# SCH_QR_Code_Scanning_Kiosk_PCB_V3_MKR_20.net
KiCad netlist of a schematic drawn in EasyEDA
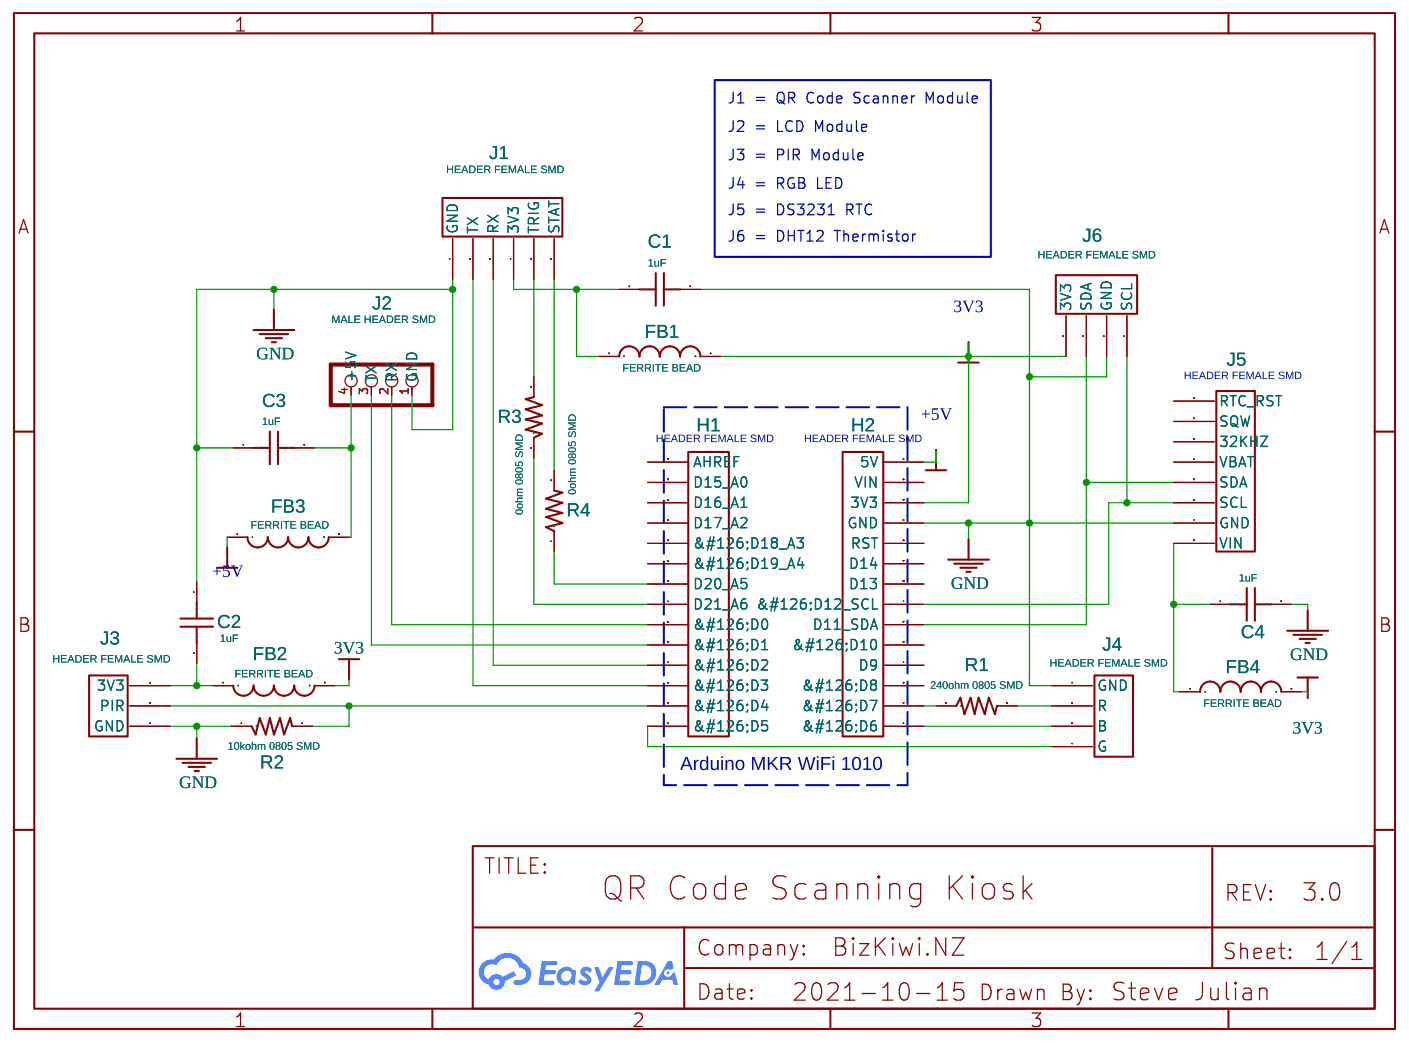
[diagram p0: schematic sheet]

(export (version "E")
  (design (tool "Eeschema 10.0.6"))
  (components
    (comp (ref "C1")
      (value "1uF")
      (fields
        (field (name "BOM_Manufacturer Part") "C0805X104K5RACAUTO")
        (field (name "BOM_Supplier Part") "C141172")
      )
      (libsource (lib "") (part "CAPACITOR CERAMIC 0805 100NF_2"))
    )
    (comp (ref "C2")
      (value "1uF")
      (fields
        (field (name "BOM_Manufacturer Part") "C0805X104K5RACAUTO")
        (field (name "BOM_Supplier Part") "C141172")
      )
      (libsource (lib "") (part "CAPACITOR CERAMIC 0805 100NF"))
    )
    (comp (ref "C3")
      (value "1uF")
      (fields
        (field (name "BOM_Manufacturer Part") "C0805X104K5RACAUTO")
        (field (name "BOM_Supplier Part") "C141172")
      )
      (libsource (lib "") (part "CAPACITOR CERAMIC 0805 100NF_1"))
    )
    (comp (ref "C4")
      (value "1uF")
      (fields
        (field (name "BOM_Manufacturer Part") "C0805X104K5RACAUTO")
        (field (name "BOM_Supplier Part") "C141172")
      )
      (libsource (lib "") (part "CAPACITOR CERAMIC 0805 100NF_2"))
    )
    (comp (ref "FB1") (value "FERRITE BEAD") (libsource (lib "") (part "FERRITE-BEADB")))
    (comp (ref "FB2") (value "FERRITE BEAD") (libsource (lib "") (part "FERRITE-BEADB_1")))
    (comp (ref "FB3") (value "FERRITE BEAD") (libsource (lib "") (part "FERRITE-BEADB_1")))
    (comp (ref "FB4") (value "FERRITE BEAD") (libsource (lib "") (part "FERRITE-BEADB")))
    (comp (ref "H1")
      (value "HEADER FEMALE 2.54MM 1X14 SMD TYPES 1 AND 2")
      (fields
        (field (name "BOM_Manufacturer Part") "SSM-116-L-SV-BE")
        (field (name "BOM_Supplier Part") "SAM11901-ND")
      )
      (libsource (lib "") (part "Unknown_570_-352"))
    )
    (comp (ref "H2")
      (value "HEADER FEMALE 2.54MM 1X14 SMD TYPES 1 AND 2")
      (fields
        (field (name "BOM_Manufacturer Part") "SSM-116-L-SV-BE")
        (field (name "BOM_Supplier Part") "SAM11901-ND")
      )
      (libsource (lib "") (part "Unknown_680_-352"))
    )
    (comp (ref "J1")
      (value "HEADER FEMALE SMD")
      (fields
        (field (name "BOM_Manufacturer Part") "SSM-116-L-SV-BE")
        (field (name "BOM_Supplier Part") "SAM11901-ND")
      )
      (libsource (lib "") (part "HEADER FEMALE 2.54MM 1X6 SMD TYPES 1 AND 2"))
    )
    (comp (ref "J2") (value "MALE HEADER SMD") (libsource (lib "") (part "MALE_HEADER_SMD_1X04")))
    (comp (ref "J3")
      (value "HEADER FEMALE SMD")
      (fields
        (field (name "BOM_Manufacturer Part") "SSM-116-L-SV-BE")
        (field (name "BOM_Supplier Part") "SAM11901-ND")
      )
      (libsource (lib "") (part "HEADER FEMALE 2.54MM 1X3 SMD TYPES 1 AND 2"))
    )
    (comp (ref "J4")
      (value "HEADER FEMALE SMD")
      (fields
        (field (name "BOM_Manufacturer Part") "SSM-116-L-SV-BE")
        (field (name "BOM_Supplier Part") "SAM11901-ND")
      )
      (libsource (lib "") (part "HEADER FEMALE 2.54MM 1X4 SMD TYPES 1 AND 2_1"))
    )
    (comp (ref "J5")
      (value "HEADER FEMALE 2.54MM 1X8 SMD TYPES 1 AND 2")
      (fields
        (field (name "BOM_Manufacturer Part") "SSM-116-L-SV-BE")
        (field (name "BOM_Supplier Part") "SAM11901-ND")
      )
      (libsource (lib "") (part "HEADER FEMALE 2.54MM 1X8 SMD TYPES 1 AND 2"))
    )
    (comp (ref "J6")
      (value "HEADER FEMALE SMD")
      (fields
        (field (name "BOM_Manufacturer Part") "SSM-116-L-SV-BE")
        (field (name "BOM_Supplier Part") "SAM11901-ND")
      )
      (libsource (lib "") (part "HEADER FEMALE 2.54MM 1X4 SMD TYPES 1 AND 2"))
    )
    (comp (ref "R1")
      (value "240ohm 0805 SMD")
      (fields
        (field (name "BOM_Manufacturer Part") "RC0805FR-07120RL")
        (field (name "BOM_Supplier Part") "311-120CRCT-ND")
      )
      (libsource (lib "") (part "120ohm 1/8W 0805 SMD_1"))
    )
    (comp (ref "R2")
      (value "10kohm 0805 SMD")
      (fields
        (field (name "BOM_Manufacturer Part") "RC0805FR-07120RL")
        (field (name "BOM_Supplier Part") "311-120CRCT-ND")
      )
      (libsource (lib "") (part "120ohm 1/8W 0805 SMD"))
    )
    (comp (ref "R3")
      (value "0ohm 0805 SMD")
      (fields
        (field (name "BOM_Manufacturer Part") "RC0805FR-07120RL")
        (field (name "BOM_Supplier Part") "311-120CRCT-ND")
      )
      (libsource (lib "") (part "120ohm 1/8W 0805 SMD_2"))
    )
    (comp (ref "R4")
      (value "0ohm 0805 SMD")
      (fields
        (field (name "BOM_Manufacturer Part") "RC0805FR-07120RL")
        (field (name "BOM_Supplier Part") "311-120CRCT-ND")
      )
      (libsource (lib "") (part "120ohm 1/8W 0805 SMD_3"))
    )
  )
  (nets
    (net (code "1") (name "+5V") (class "Default")
      (node (ref "FB3") (pin "1") (pinfunction "1_1") (pintype "unspecified"))
      (node (ref "H2") (pin "14") (pinfunction "5V_14") (pintype "input"))
    )
    (net (code "2") (name "3V3") (class "Default")
      (node (ref "FB1") (pin "2") (pinfunction "2_2") (pintype "unspecified"))
      (node (ref "FB2") (pin "2") (pinfunction "2_2") (pintype "unspecified"))
      (node (ref "FB4") (pin "2") (pinfunction "2_2") (pintype "unspecified"))
      (node (ref "H2") (pin "12") (pinfunction "3V3_12") (pintype "input"))
      (node (ref "J6") (pin "1") (pinfunction "3V3_1") (pintype "input"))
    )
    (net (code "3") (name "GND") (class "Default")
      (node (ref "C1") (pin "2") (pinfunction "2_2") (pintype "unspecified"))
      (node (ref "C2") (pin "1") (pinfunction "1_1") (pintype "unspecified"))
      (node (ref "C3") (pin "1") (pinfunction "1_1") (pintype "unspecified"))
      (node (ref "C4") (pin "2") (pinfunction "2_2") (pintype "unspecified"))
      (node (ref "H2") (pin "11") (pinfunction "GND_11") (pintype "input"))
      (node (ref "J1") (pin "1") (pinfunction "GND_1") (pintype "passive"))
      (node (ref "J2") (pin "1") (pinfunction "GND_1") (pintype "unspecified"))
      (node (ref "J3") (pin "1") (pinfunction "GND_1") (pintype "input"))
      (node (ref "J4") (pin "1") (pinfunction "GND_1") (pintype "input"))
      (node (ref "J5") (pin "7") (pinfunction "GND_7") (pintype "input"))
      (node (ref "J6") (pin "3") (pinfunction "GND_3") (pintype "input"))
      (node (ref "R2") (pin "1") (pinfunction "1_1") (pintype "unspecified"))
    )
    (net (code "4") (name "Net-(H1-&#126;D0)") (class "Default")
      (node (ref "H1") (pin "6") (pinfunction "&#126;D0_6") (pintype "input"))
      (node (ref "J2") (pin "2") (pinfunction "RX_2") (pintype "unspecified"))
    )
    (net (code "5") (name "Net-(H1-&#126;D1)") (class "Default")
      (node (ref "H1") (pin "5") (pinfunction "&#126;D1_5") (pintype "input"))
      (node (ref "J2") (pin "3") (pinfunction "TX_3") (pintype "unspecified"))
    )
    (net (code "6") (name "Net-(H1-&#126;D2)") (class "Default")
      (node (ref "H1") (pin "4") (pinfunction "&#126;D2_4") (pintype "input"))
      (node (ref "J1") (pin "3") (pinfunction "RX_3") (pintype "input"))
    )
    (net (code "7") (name "Net-(H1-&#126;D3)") (class "Default")
      (node (ref "H1") (pin "3") (pinfunction "&#126;D3_3") (pintype "input"))
      (node (ref "J1") (pin "2") (pinfunction "TX_2") (pintype "output"))
    )
    (net (code "8") (name "Net-(H1-&#126;D4)") (class "Default")
      (node (ref "H1") (pin "2") (pinfunction "&#126;D4_2") (pintype "input"))
      (node (ref "J3") (pin "2") (pinfunction "PIR_2") (pintype "input"))
      (node (ref "R2") (pin "2") (pinfunction "2_2") (pintype "unspecified"))
    )
    (net (code "9") (name "Net-(H1-&#126;D5)") (class "Default")
      (node (ref "H1") (pin "1") (pinfunction "&#126;D5_1") (pintype "input"))
      (node (ref "J4") (pin "4") (pinfunction "G_4") (pintype "input"))
    )
    (net (code "10") (name "Net-(H1-D20_A5)") (class "Default")
      (node (ref "H1") (pin "8") (pinfunction "D20_A5_8") (pintype "input"))
      (node (ref "R4") (pin "1") (pinfunction "1_1") (pintype "unspecified"))
    )
    (net (code "11") (name "Net-(H1-D21_A6)") (class "Default")
      (node (ref "H1") (pin "7") (pinfunction "D21_A6_7") (pintype "input"))
      (node (ref "R3") (pin "1") (pinfunction "1_1") (pintype "unspecified"))
    )
    (net (code "12") (name "Net-(H2-&#126;D6)") (class "Default")
      (node (ref "H2") (pin "1") (pinfunction "&#126;D6_1") (pintype "input"))
      (node (ref "J4") (pin "3") (pinfunction "B_3") (pintype "input"))
    )
    (net (code "13") (name "Net-(H2-&#126;D7)") (class "Default")
      (node (ref "H2") (pin "2") (pinfunction "&#126;D7_2") (pintype "input"))
      (node (ref "R1") (pin "1") (pinfunction "1_1") (pintype "unspecified"))
    )
    (net (code "14") (name "Net-(H2-&#126;D12_SCL)") (class "Default")
      (node (ref "H2") (pin "7") (pinfunction "&#126;D12_SCL_7") (pintype "input"))
      (node (ref "J5") (pin "6") (pinfunction "SCL_6") (pintype "input"))
      (node (ref "J6") (pin "4") (pinfunction "SCL_4") (pintype "input"))
    )
    (net (code "15") (name "Net-(H2-D11_SDA)") (class "Default")
      (node (ref "H2") (pin "6") (pinfunction "D11_SDA_6") (pintype "input"))
      (node (ref "J5") (pin "5") (pinfunction "SDA_5") (pintype "input"))
      (node (ref "J6") (pin "2") (pinfunction "SDA_2") (pintype "input"))
    )
    (net (code "16") (name "Net-(J1-3V3)") (class "Default")
      (node (ref "C1") (pin "1") (pinfunction "1_1") (pintype "unspecified"))
      (node (ref "FB1") (pin "1") (pinfunction "1_1") (pintype "unspecified"))
      (node (ref "J1") (pin "4") (pinfunction "3V3_4") (pintype "passive"))
    )
    (net (code "17") (name "Net-(J1-STAT)") (class "Default")
      (node (ref "J1") (pin "6") (pinfunction "STAT_6") (pintype "output"))
      (node (ref "R4") (pin "2") (pinfunction "2_2") (pintype "unspecified"))
    )
    (net (code "18") (name "Net-(J1-TRIG)") (class "Default")
      (node (ref "J1") (pin "5") (pinfunction "TRIG_5") (pintype "input"))
      (node (ref "R3") (pin "2") (pinfunction "2_2") (pintype "unspecified"))
    )
    (net (code "19") (name "Net-(J2-+5V)") (class "Default")
      (node (ref "C3") (pin "2") (pinfunction "2_2") (pintype "unspecified"))
      (node (ref "FB3") (pin "2") (pinfunction "2_2") (pintype "unspecified"))
      (node (ref "J2") (pin "4") (pinfunction "+5V_4") (pintype "passive"))
    )
    (net (code "20") (name "Net-(J3-3V3)") (class "Default")
      (node (ref "C2") (pin "2") (pinfunction "2_2") (pintype "unspecified"))
      (node (ref "FB2") (pin "1") (pinfunction "1_1") (pintype "unspecified"))
      (node (ref "J3") (pin "3") (pinfunction "3V3_3") (pintype "input"))
    )
    (net (code "21") (name "Net-(J4-R)") (class "Default")
      (node (ref "J4") (pin "2") (pinfunction "R_2") (pintype "input"))
      (node (ref "R1") (pin "2") (pinfunction "2_2") (pintype "unspecified"))
    )
    (net (code "22") (name "Net-(J5-VIN)") (class "Default")
      (node (ref "C4") (pin "1") (pinfunction "1_1") (pintype "unspecified"))
      (node (ref "FB4") (pin "1") (pinfunction "1_1") (pintype "unspecified"))
      (node (ref "J5") (pin "8") (pinfunction "VIN_8") (pintype "input"))
    )
    (net (code "23") (name "unconnected-(H1-&#126;D18_A3-Pad10)") (class "Default")
      (node (ref "H1") (pin "10") (pinfunction "&#126;D18_A3_10") (pintype "input"))
    )
    (net (code "24") (name "unconnected-(H1-&#126;D19_A4-Pad9)") (class "Default")
      (node (ref "H1") (pin "9") (pinfunction "&#126;D19_A4_9") (pintype "input"))
    )
    (net (code "25") (name "unconnected-(H1-AHREF-Pad14)") (class "Default")
      (node (ref "H1") (pin "14") (pinfunction "AHREF_14") (pintype "input"))
    )
    (net (code "26") (name "unconnected-(H1-D15_A0-Pad13)") (class "Default")
      (node (ref "H1") (pin "13") (pinfunction "D15_A0_13") (pintype "input"))
    )
    (net (code "27") (name "unconnected-(H1-D16_A1-Pad12)") (class "Default")
      (node (ref "H1") (pin "12") (pinfunction "D16_A1_12") (pintype "input"))
    )
    (net (code "28") (name "unconnected-(H1-D17_A2-Pad11)") (class "Default")
      (node (ref "H1") (pin "11") (pinfunction "D17_A2_11") (pintype "input"))
    )
    (net (code "29") (name "unconnected-(H2-&#126;D8-Pad3)") (class "Default")
      (node (ref "H2") (pin "3") (pinfunction "&#126;D8_3") (pintype "input"))
    )
    (net (code "30") (name "unconnected-(H2-&#126;D10-Pad5)") (class "Default")
      (node (ref "H2") (pin "5") (pinfunction "&#126;D10_5") (pintype "input"))
    )
    (net (code "31") (name "unconnected-(H2-D9-Pad4)") (class "Default")
      (node (ref "H2") (pin "4") (pinfunction "D9_4") (pintype "input"))
    )
    (net (code "32") (name "unconnected-(H2-D13-Pad8)") (class "Default")
      (node (ref "H2") (pin "8") (pinfunction "D13_8") (pintype "input"))
    )
    (net (code "33") (name "unconnected-(H2-D14-Pad9)") (class "Default")
      (node (ref "H2") (pin "9") (pinfunction "D14_9") (pintype "input"))
    )
    (net (code "34") (name "unconnected-(H2-RST-Pad10)") (class "Default")
      (node (ref "H2") (pin "10") (pinfunction "RST_10") (pintype "input"))
    )
    (net (code "35") (name "unconnected-(H2-VIN-Pad13)") (class "Default")
      (node (ref "H2") (pin "13") (pinfunction "VIN_13") (pintype "input"))
    )
    (net (code "36") (name "unconnected-(J5-32KHZ-Pad3)") (class "Default")
      (node (ref "J5") (pin "3") (pinfunction "32KHZ_3") (pintype "input"))
    )
    (net (code "37") (name "unconnected-(J5-RTC_RST-Pad1)") (class "Default")
      (node (ref "J5") (pin "1") (pinfunction "RTC_RST_1") (pintype "input"))
    )
    (net (code "38") (name "unconnected-(J5-SQW-Pad2)") (class "Default")
      (node (ref "J5") (pin "2") (pinfunction "SQW_2") (pintype "input"))
    )
    (net (code "39") (name "unconnected-(J5-VBAT-Pad4)") (class "Default")
      (node (ref "J5") (pin "4") (pinfunction "VBAT_4") (pintype "input"))
    )
  )
)
